# Dimmer_RevA.net
KiCad netlist of a schematic drawn in EAGLE
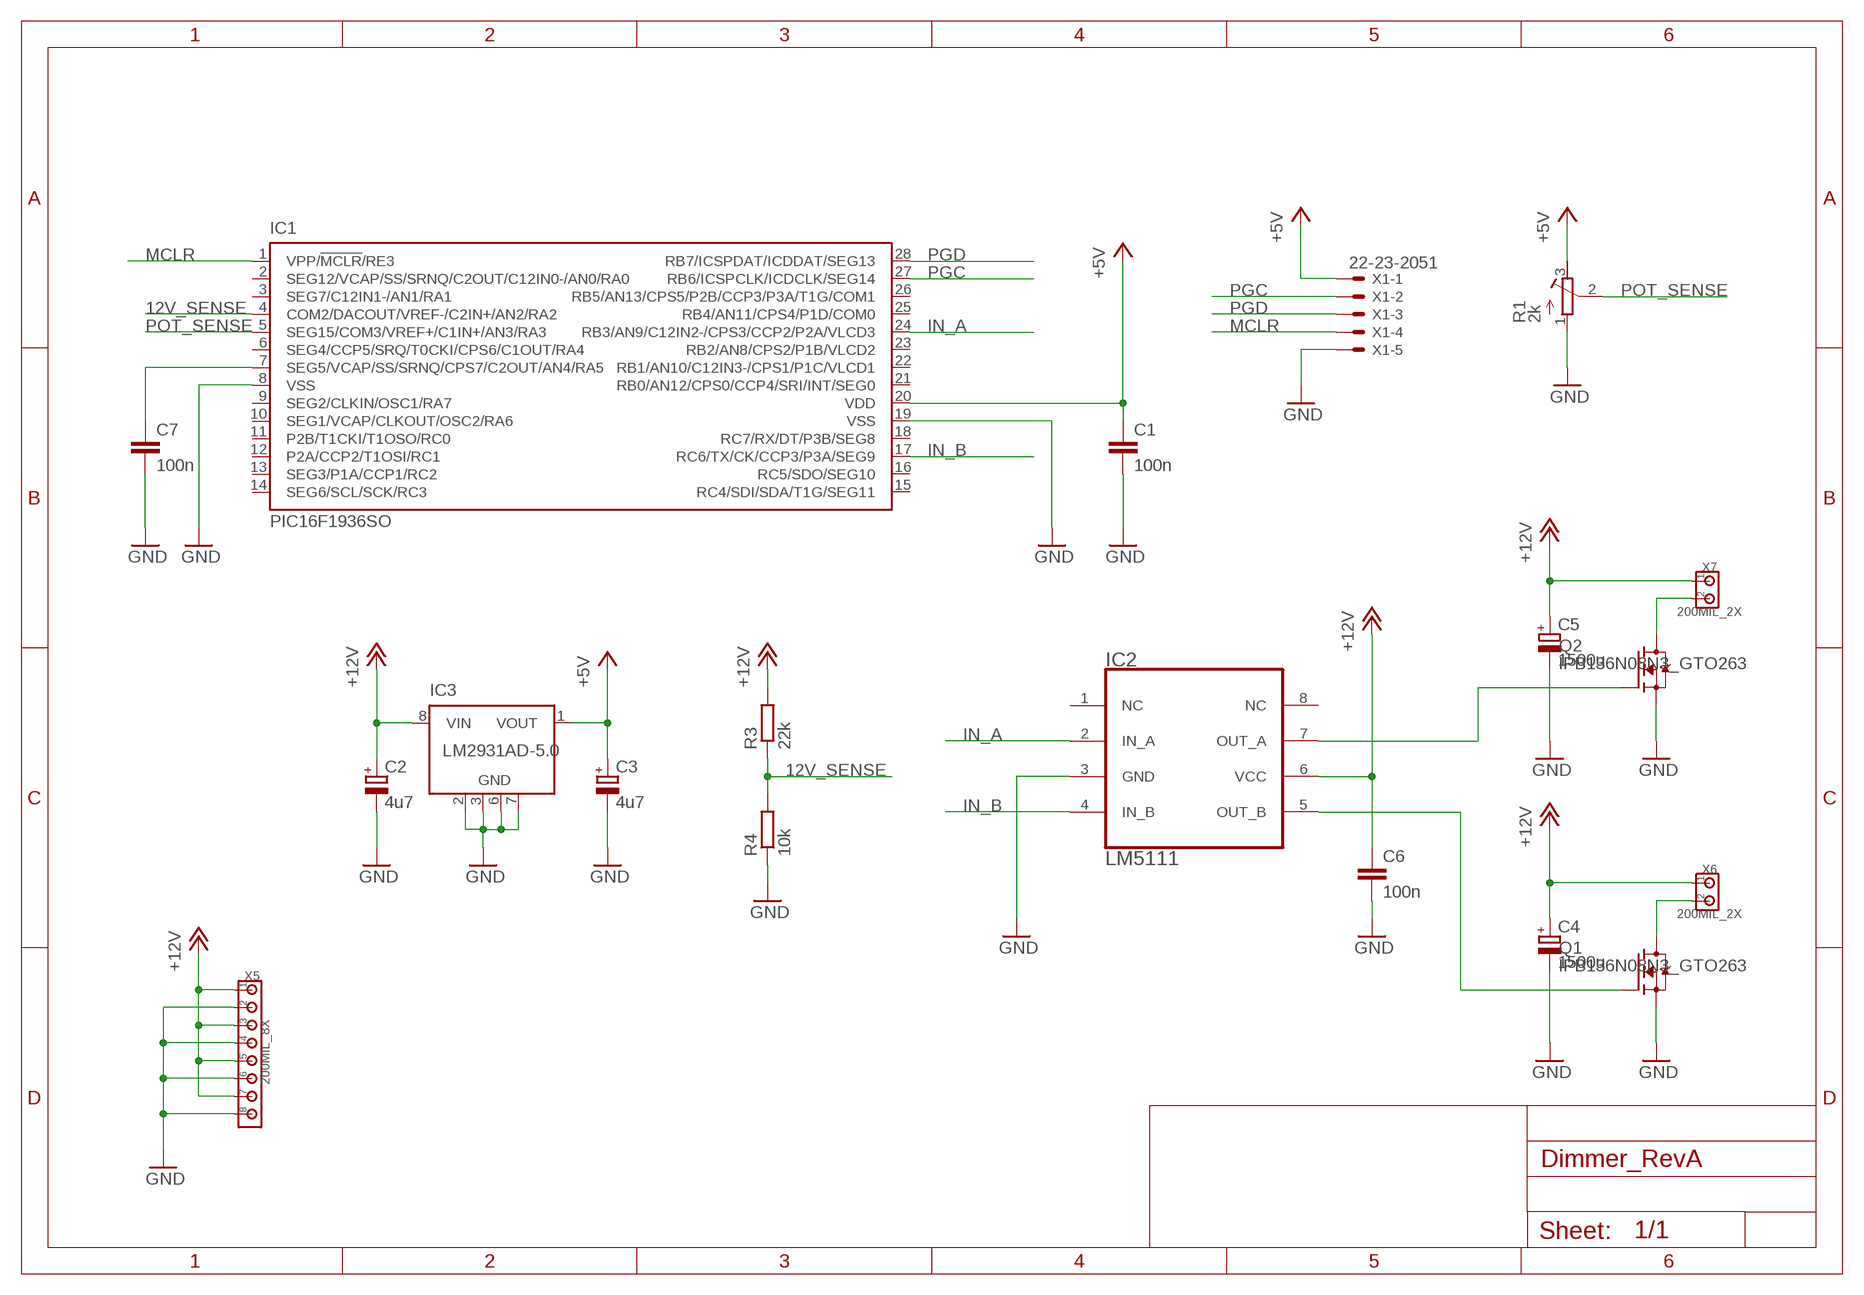
[diagram p0: schematic, sheet 1]

(export (version "E")
  (design (tool "Eeschema 10.0.6"))
  (components
    (comp (ref "C1")
      (value "100n")
      (footprint "eagle-import:C0805")
      (libsource (lib "eagle-import") (part "CC0805"))
    )
    (comp (ref "C2")
      (value "4u7")
      (footprint "eagle-import:SMC_C")
      (libsource (lib "eagle-import") (part "C_POLARIZEDSMC_C"))
    )
    (comp (ref "C3")
      (value "4u7")
      (footprint "eagle-import:SMC_C")
      (libsource (lib "eagle-import") (part "C_POLARIZEDSMC_C"))
    )
    (comp (ref "C4")
      (value "1500u")
      (footprint "eagle-import:10MM")
      (libsource (lib "eagle-import") (part "C_POLARIZED10MM"))
    )
    (comp (ref "C5")
      (value "1500u")
      (footprint "eagle-import:10MM")
      (libsource (lib "eagle-import") (part "C_POLARIZED10MM"))
    )
    (comp (ref "C6")
      (value "100n")
      (footprint "eagle-import:C0805")
      (libsource (lib "eagle-import") (part "CC0805"))
    )
    (comp (ref "C7")
      (value "100n")
      (footprint "eagle-import:C0805")
      (libsource (lib "eagle-import") (part "CC0805"))
    )
    (comp (ref "IC1")
      (value "PIC16F1936SO")
      (footprint "eagle-import:SO28W")
      (libsource (lib "eagle-import") (part "PIC16F19SO36"))
    )
    (comp (ref "IC2")
      (value "LM5111")
      (footprint "eagle-import:SOIC8")
      (libsource (lib "eagle-import") (part "LM5111"))
    )
    (comp (ref "IC3")
      (value "LM2931AD-5.0")
      (footprint "eagle-import:SO8")
      (libsource (lib "eagle-import") (part "LM2931AD-5.0"))
    )
    (comp (ref "Q1")
      (value "IPB136N08N3_GTO263")
      (footprint "eagle-import:TO263-3")
      (libsource (lib "eagle-import") (part "IPB136N08N3_GTO263"))
    )
    (comp (ref "Q2")
      (value "IPB136N08N3_GTO263")
      (footprint "eagle-import:TO263-3")
      (libsource (lib "eagle-import") (part "IPB136N08N3_GTO263"))
    )
    (comp (ref "R1")
      (value "2k")
      (footprint "eagle-import:CONTELEC")
      (libsource (lib "eagle-import") (part "TRIMMER"))
    )
    (comp (ref "R3")
      (value "22k")
      (footprint "eagle-import:R0805")
      (libsource (lib "eagle-import") (part "RESISTORR0805"))
    )
    (comp (ref "R4")
      (value "10k")
      (footprint "eagle-import:R0805")
      (libsource (lib "eagle-import") (part "RESISTORR0805"))
    )
    (comp (ref "X1")
      (value "22-23-2051")
      (footprint "eagle-import:22-23-2051")
      (fields (field (name "MF") "MOLEX"))
      (libsource (lib "eagle-import") (part "22-23-2051"))
    )
    (comp (ref "X5")
      (value "200MIL_8X")
      (footprint "eagle-import:200MIL_8X")
      (libsource (lib "eagle-import") (part "200MIL_8X"))
    )
    (comp (ref "X6")
      (value "200MIL_2X")
      (footprint "eagle-import:200MIL_2X")
      (libsource (lib "eagle-import") (part "200MIL_2X"))
    )
    (comp (ref "X7")
      (value "200MIL_2X")
      (footprint "eagle-import:200MIL_2X")
      (libsource (lib "eagle-import") (part "200MIL_2X"))
    )
  )
  (nets
    (net (code "1") (name "+5V") (class "Default")
      (node (ref "C1") (pin "1") (pinfunction "1_1") (pintype "passive"))
      (node (ref "C3") (pin "+") (pinfunction "+_+") (pintype "passive"))
      (node (ref "IC1") (pin "20") (pinfunction "VDD_20") (pintype "power_in"))
      (node (ref "IC3") (pin "1") (pinfunction "VOUT_1") (pintype "output"))
      (node (ref "R1") (pin "3") (pinfunction "CW_3") (pintype "passive"))
      (node (ref "X1") (pin "1") (pinfunction "S_1") (pintype "passive"))
    )
    (net (code "2") (name "+12V") (class "Default")
      (node (ref "C2") (pin "+") (pinfunction "+_+") (pintype "passive"))
      (node (ref "C4") (pin "+") (pinfunction "+_+") (pintype "passive"))
      (node (ref "C5") (pin "+") (pinfunction "+_+") (pintype "passive"))
      (node (ref "C6") (pin "1") (pinfunction "1_1") (pintype "passive"))
      (node (ref "IC2") (pin "6") (pinfunction "VCC_6") (pintype "input"))
      (node (ref "IC3") (pin "8") (pinfunction "VIN_8") (pintype "passive"))
      (node (ref "R3") (pin "2") (pinfunction "2_2") (pintype "passive"))
      (node (ref "X5") (pin "1") (pinfunction "P$1_1") (pintype "passive"))
      (node (ref "X5") (pin "3") (pinfunction "P$3_3") (pintype "passive"))
      (node (ref "X5") (pin "5") (pinfunction "P$5_5") (pintype "passive"))
      (node (ref "X5") (pin "7") (pinfunction "P$7_7") (pintype "passive"))
      (node (ref "X6") (pin "1") (pinfunction "1_1") (pintype "passive"))
      (node (ref "X7") (pin "1") (pinfunction "1_1") (pintype "passive"))
    )
    (net (code "3") (name "/12V_SENSE") (class "Default")
      (node (ref "IC1") (pin "4") (pinfunction "COM2/DACOUT/VREF-/C2IN+/AN2/RA2_4") (pintype "bidirectional"))
      (node (ref "R3") (pin "1") (pinfunction "1_1") (pintype "passive"))
      (node (ref "R4") (pin "2") (pinfunction "2_2") (pintype "passive"))
    )
    (net (code "4") (name "/IN_A") (class "Default")
      (node (ref "IC1") (pin "24") (pinfunction "RB3/AN9/C12IN2-/CPS3/CCP2/P2A/VLCD3_24") (pintype "bidirectional"))
      (node (ref "IC2") (pin "2") (pinfunction "IN_A_2") (pintype "input"))
    )
    (net (code "5") (name "/IN_B") (class "Default")
      (node (ref "IC1") (pin "17") (pinfunction "RC6/TX/CK/CCP3/P3A/SEG9_17") (pintype "bidirectional"))
      (node (ref "IC2") (pin "4") (pinfunction "IN_B_4") (pintype "passive"))
    )
    (net (code "6") (name "/MCLR") (class "Default")
      (node (ref "IC1") (pin "1") (pinfunction "VPP/~{MCLR}/RE3_1") (pintype "input"))
      (node (ref "X1") (pin "4") (pinfunction "S_4") (pintype "passive"))
    )
    (net (code "7") (name "/NC") (class "Default")
      (node (ref "IC2") (pin "8") (pinfunction "NC_8") (pintype "power_in"))
    )
    (net (code "8") (name "/PGC") (class "Default")
      (node (ref "IC1") (pin "27") (pinfunction "RB6/ICSPCLK/ICDCLK/SEG14_27") (pintype "bidirectional"))
      (node (ref "X1") (pin "2") (pinfunction "S_2") (pintype "passive"))
    )
    (net (code "9") (name "/PGD") (class "Default")
      (node (ref "IC1") (pin "28") (pinfunction "RB7/ICSPDAT/ICDDAT/SEG13_28") (pintype "bidirectional"))
      (node (ref "X1") (pin "3") (pinfunction "S_3") (pintype "passive"))
    )
    (net (code "10") (name "/POT_SENSE") (class "Default")
      (node (ref "IC1") (pin "5") (pinfunction "SEG15/COM3/VREF+/C1IN+/AN3/RA3_5") (pintype "bidirectional"))
      (node (ref "R1") (pin "2") (pinfunction "WIPER_2") (pintype "passive"))
    )
    (net (code "11") (name "GND") (class "Default")
      (node (ref "C1") (pin "2") (pinfunction "2_2") (pintype "passive"))
      (node (ref "C2") (pin "-") (pinfunction "-_-") (pintype "passive"))
      (node (ref "C3") (pin "-") (pinfunction "-_-") (pintype "passive"))
      (node (ref "C4") (pin "-") (pinfunction "-_-") (pintype "passive"))
      (node (ref "C5") (pin "-") (pinfunction "-_-") (pintype "passive"))
      (node (ref "C6") (pin "2") (pinfunction "2_2") (pintype "passive"))
      (node (ref "C7") (pin "2") (pinfunction "2_2") (pintype "passive"))
      (node (ref "IC1") (pin "19") (pinfunction "VSS_19") (pintype "power_in"))
      (node (ref "IC1") (pin "8") (pinfunction "VSS_8") (pintype "power_in"))
      (node (ref "IC2") (pin "3") (pinfunction "GND_3") (pintype "input"))
      (node (ref "IC3") (pin "2") (pinfunction "GND_2") (pintype "power_in"))
      (node (ref "IC3") (pin "3") (pinfunction "GND_3") (pintype "power_in"))
      (node (ref "IC3") (pin "6") (pinfunction "GND_6") (pintype "power_in"))
      (node (ref "IC3") (pin "7") (pinfunction "GND_7") (pintype "power_in"))
      (node (ref "Q1") (pin "3") (pinfunction "S_3") (pintype "passive"))
      (node (ref "Q2") (pin "3") (pinfunction "S_3") (pintype "passive"))
      (node (ref "R1") (pin "1") (pinfunction "CCW_1") (pintype "passive"))
      (node (ref "R4") (pin "1") (pinfunction "1_1") (pintype "passive"))
      (node (ref "X1") (pin "5") (pinfunction "S_5") (pintype "passive"))
      (node (ref "X5") (pin "2") (pinfunction "P$2_2") (pintype "passive"))
      (node (ref "X5") (pin "4") (pinfunction "P$4_4") (pintype "passive"))
      (node (ref "X5") (pin "6") (pinfunction "P$6_6") (pintype "passive"))
      (node (ref "X5") (pin "8") (pinfunction "P$8_8") (pintype "passive"))
    )
    (net (code "12") (name "Net-(IC1-SEG5{slash}VCAP{slash}SS{slash}SRNQ{slash}CPS7{slash}C2OUT{slash}AN4{slash}RA5)") (class "Default")
      (node (ref "C7") (pin "1") (pinfunction "1_1") (pintype "passive"))
      (node (ref "IC1") (pin "7") (pinfunction "SEG5/VCAP/SS/SRNQ/CPS7/C2OUT/AN4/RA5_7") (pintype "bidirectional"))
    )
    (net (code "13") (name "Net-(IC2-OUT_A)") (class "Default")
      (node (ref "IC2") (pin "7") (pinfunction "OUT_A_7") (pintype "input"))
      (node (ref "Q2") (pin "1") (pinfunction "G_1") (pintype "passive"))
    )
    (net (code "14") (name "Net-(IC2-OUT_B)") (class "Default")
      (node (ref "IC2") (pin "5") (pinfunction "OUT_B_5") (pintype "bidirectional"))
      (node (ref "Q1") (pin "1") (pinfunction "G_1") (pintype "passive"))
    )
    (net (code "15") (name "Net-(Q1-D)") (class "Default")
      (node (ref "Q1") (pin "TAB") (pinfunction "D_TAB") (pintype "passive"))
      (node (ref "X6") (pin "2") (pinfunction "2_2") (pintype "passive"))
    )
    (net (code "16") (name "Net-(Q2-D)") (class "Default")
      (node (ref "Q2") (pin "TAB") (pinfunction "D_TAB") (pintype "passive"))
      (node (ref "X7") (pin "2") (pinfunction "2_2") (pintype "passive"))
    )
    (net (code "17") (name "unconnected-(IC1-P2A{slash}CCP2{slash}T1OSI{slash}RC1-Pad12)") (class "Default")
      (node (ref "IC1") (pin "12") (pinfunction "P2A/CCP2/T1OSI/RC1_12") (pintype "bidirectional"))
    )
    (net (code "18") (name "unconnected-(IC1-P2B{slash}T1CKI{slash}T1OSO{slash}RC0-Pad11)") (class "Default")
      (node (ref "IC1") (pin "11") (pinfunction "P2B/T1CKI/T1OSO/RC0_11") (pintype "bidirectional"))
    )
    (net (code "19") (name "unconnected-(IC1-RB0{slash}AN12{slash}CPS0{slash}CCP4{slash}SRI{slash}INT{slash}SEG0-Pad21)") (class "Default")
      (node (ref "IC1") (pin "21") (pinfunction "RB0/AN12/CPS0/CCP4/SRI/INT/SEG0_21") (pintype "bidirectional"))
    )
    (net (code "20") (name "unconnected-(IC1-RB1{slash}AN10{slash}C12IN3-{slash}CPS1{slash}P1C{slash}VLCD1-Pad22)") (class "Default")
      (node (ref "IC1") (pin "22") (pinfunction "RB1/AN10/C12IN3-/CPS1/P1C/VLCD1_22") (pintype "bidirectional"))
    )
    (net (code "21") (name "unconnected-(IC1-RB2{slash}AN8{slash}CPS2{slash}P1B{slash}VLCD2-Pad23)") (class "Default")
      (node (ref "IC1") (pin "23") (pinfunction "RB2/AN8/CPS2/P1B/VLCD2_23") (pintype "bidirectional"))
    )
    (net (code "22") (name "unconnected-(IC1-RB4{slash}AN11{slash}CPS4{slash}P1D{slash}COM0-Pad25)") (class "Default")
      (node (ref "IC1") (pin "25") (pinfunction "RB4/AN11/CPS4/P1D/COM0_25") (pintype "bidirectional"))
    )
    (net (code "23") (name "unconnected-(IC1-RB5{slash}AN13{slash}CPS5{slash}P2B{slash}CCP3{slash}P3A{slash}T1G{slash}COM1-Pad26)") (class "Default")
      (node (ref "IC1") (pin "26") (pinfunction "RB5/AN13/CPS5/P2B/CCP3/P3A/T1G/COM1_26") (pintype "bidirectional"))
    )
    (net (code "24") (name "unconnected-(IC1-RC4{slash}SDI{slash}SDA{slash}T1G{slash}SEG11-Pad15)") (class "Default")
      (node (ref "IC1") (pin "15") (pinfunction "RC4/SDI/SDA/T1G/SEG11_15") (pintype "bidirectional"))
    )
    (net (code "25") (name "unconnected-(IC1-RC5{slash}SDO{slash}SEG10-Pad16)") (class "Default")
      (node (ref "IC1") (pin "16") (pinfunction "RC5/SDO/SEG10_16") (pintype "bidirectional"))
    )
    (net (code "26") (name "unconnected-(IC1-RC7{slash}RX{slash}DT{slash}P3B{slash}SEG8-Pad18)") (class "Default")
      (node (ref "IC1") (pin "18") (pinfunction "RC7/RX/DT/P3B/SEG8_18") (pintype "bidirectional"))
    )
    (net (code "27") (name "unconnected-(IC1-SEG1{slash}VCAP{slash}CLKOUT{slash}OSC2{slash}RA6-Pad10)") (class "Default")
      (node (ref "IC1") (pin "10") (pinfunction "SEG1/VCAP/CLKOUT/OSC2/RA6_10") (pintype "bidirectional"))
    )
    (net (code "28") (name "unconnected-(IC1-SEG2{slash}CLKIN{slash}OSC1{slash}RA7-Pad9)") (class "Default")
      (node (ref "IC1") (pin "9") (pinfunction "SEG2/CLKIN/OSC1/RA7_9") (pintype "bidirectional"))
    )
    (net (code "29") (name "unconnected-(IC1-SEG3{slash}P1A{slash}CCP1{slash}RC2-Pad13)") (class "Default")
      (node (ref "IC1") (pin "13") (pinfunction "SEG3/P1A/CCP1/RC2_13") (pintype "bidirectional"))
    )
    (net (code "30") (name "unconnected-(IC1-SEG4{slash}CCP5{slash}SRQ{slash}T0CKI{slash}CPS6{slash}C1OUT{slash}RA4-Pad6)") (class "Default")
      (node (ref "IC1") (pin "6") (pinfunction "SEG4/CCP5/SRQ/T0CKI/CPS6/C1OUT/RA4_6") (pintype "bidirectional"))
    )
    (net (code "31") (name "unconnected-(IC1-SEG6{slash}SCL{slash}SCK{slash}RC3-Pad14)") (class "Default")
      (node (ref "IC1") (pin "14") (pinfunction "SEG6/SCL/SCK/RC3_14") (pintype "bidirectional"))
    )
    (net (code "32") (name "unconnected-(IC1-SEG7{slash}C12IN1-{slash}AN1{slash}RA1-Pad3)") (class "Default")
      (node (ref "IC1") (pin "3") (pinfunction "SEG7/C12IN1-/AN1/RA1_3") (pintype "bidirectional"))
    )
    (net (code "33") (name "unconnected-(IC1-SEG12{slash}VCAP{slash}SS{slash}SRNQ{slash}C2OUT{slash}C12IN0-{slash}AN0{slash}RA0-Pad2)") (class "Default")
      (node (ref "IC1") (pin "2") (pinfunction "SEG12/VCAP/SS/SRNQ/C2OUT/C12IN0-/AN0/RA0_2") (pintype "bidirectional"))
    )
    (net (code "34") (name "unconnected-(IC2-NC-Pad1)") (class "Default")
      (node (ref "IC2") (pin "1") (pinfunction "NC_1") (pintype "input"))
    )
  )
)
